# lcdconnector2.net
KiCad netlist of a schematic drawn in EAGLE
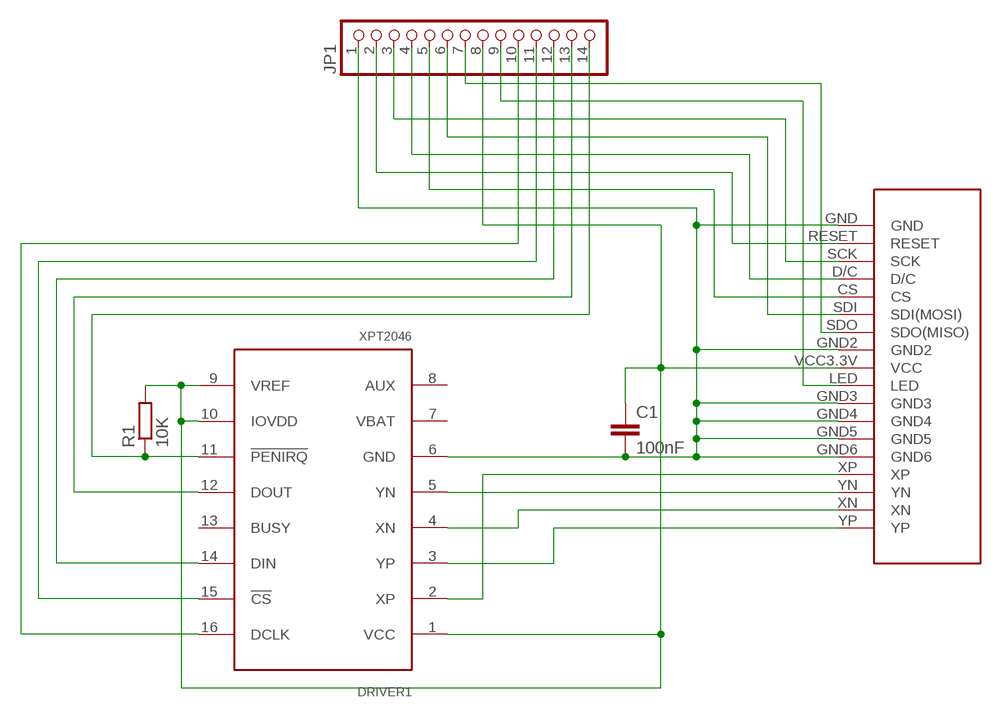
[diagram p0: schematic, sheet 1]

(export (version "E")
  (design (tool "Eeschema 10.0.6"))
  (components
    (comp (ref "C1")
      (value "100nF")
      (footprint "eagle-import:C0805K")
      (libsource (lib "eagle-import") (part "C-EUC0805K"))
    )
    (comp (ref "CONNECTOR1")
      (value "TJCTM24024-PINS")
      (footprint "eagle-import:TJCTM24024-PINS")
      (libsource (lib "eagle-import") (part "TJCTM24024-PINS"))
    )
    (comp (ref "DRIVER1")
      (value "XPT2046")
      (footprint "eagle-import:XPT2046")
      (libsource (lib "eagle-import") (part "XPT2046"))
    )
    (comp (ref "JP1")
      (value "PINHD-1X14-CB")
      (footprint "eagle-import:1X14-CB")
      (libsource (lib "eagle-import") (part "PINHD-1X14-CB"))
    )
    (comp (ref "R1")
      (value "10K")
      (footprint "eagle-import:M0805")
      (libsource (lib "eagle-import") (part "R-EU_M0805"))
    )
  )
  (nets
    (net (code "1") (name "Net-(CONNECTOR1-PadCS)") (class "Default")
      (node (ref "CONNECTOR1") (pin "CS") (pinfunction "CS_CS") (pintype "bidirectional"))
      (node (ref "JP1") (pin "5") (pinfunction "5_5") (pintype "passive"))
    )
    (net (code "2") (name "Net-(CONNECTOR1-PadD{slash}C)") (class "Default")
      (node (ref "CONNECTOR1") (pin "D/C") (pinfunction "D/C_D/C") (pintype "bidirectional"))
      (node (ref "JP1") (pin "4") (pinfunction "4_4") (pintype "passive"))
    )
    (net (code "3") (name "Net-(CONNECTOR1-PadLED)") (class "Default")
      (node (ref "CONNECTOR1") (pin "LED") (pinfunction "LED_LED") (pintype "bidirectional"))
      (node (ref "JP1") (pin "9") (pinfunction "9_9") (pintype "passive"))
    )
    (net (code "4") (name "Net-(CONNECTOR1-PadRESET)") (class "Default")
      (node (ref "CONNECTOR1") (pin "RESET") (pinfunction "RESET_RESET") (pintype "bidirectional"))
      (node (ref "JP1") (pin "2") (pinfunction "2_2") (pintype "passive"))
    )
    (net (code "5") (name "Net-(CONNECTOR1-PadSCK)") (class "Default")
      (node (ref "CONNECTOR1") (pin "SCK") (pinfunction "SCK_SCK") (pintype "bidirectional"))
      (node (ref "JP1") (pin "3") (pinfunction "3_3") (pintype "passive"))
    )
    (net (code "6") (name "Net-(CONNECTOR1-SDI(MOSI))") (class "Default")
      (node (ref "CONNECTOR1") (pin "SDI") (pinfunction "SDI(MOSI)_SDI") (pintype "bidirectional"))
      (node (ref "JP1") (pin "6") (pinfunction "6_6") (pintype "passive"))
    )
    (net (code "7") (name "Net-(CONNECTOR1-SDO(MISO))") (class "Default")
      (node (ref "CONNECTOR1") (pin "SDO") (pinfunction "SDO(MISO)_SDO") (pintype "bidirectional"))
      (node (ref "JP1") (pin "7") (pinfunction "7_7") (pintype "passive"))
    )
    (net (code "8") (name "Net-(CONNECTOR1-VCC)") (class "Default")
      (node (ref "C1") (pin "1") (pinfunction "1_1") (pintype "passive"))
      (node (ref "CONNECTOR1") (pin "VCC3.3V") (pinfunction "VCC_VCC3.3V") (pintype "bidirectional"))
      (node (ref "DRIVER1") (pin "1") (pinfunction "VCC_1") (pintype "bidirectional"))
      (node (ref "DRIVER1") (pin "10") (pinfunction "IOVDD_10") (pintype "bidirectional"))
      (node (ref "DRIVER1") (pin "9") (pinfunction "VREF_9") (pintype "bidirectional"))
      (node (ref "JP1") (pin "8") (pinfunction "8_8") (pintype "passive"))
      (node (ref "R1") (pin "2") (pinfunction "2_2") (pintype "passive"))
    )
    (net (code "9") (name "Net-(DRIVER1-DCLK)") (class "Default")
      (node (ref "DRIVER1") (pin "16") (pinfunction "DCLK_16") (pintype "bidirectional"))
      (node (ref "JP1") (pin "10") (pinfunction "10_10") (pintype "passive"))
    )
    (net (code "10") (name "Net-(DRIVER1-DIN)") (class "Default")
      (node (ref "DRIVER1") (pin "14") (pinfunction "DIN_14") (pintype "bidirectional"))
      (node (ref "JP1") (pin "12") (pinfunction "12_12") (pintype "passive"))
    )
    (net (code "11") (name "Net-(DRIVER1-DOUT)") (class "Default")
      (node (ref "DRIVER1") (pin "12") (pinfunction "DOUT_12") (pintype "bidirectional"))
      (node (ref "JP1") (pin "13") (pinfunction "13_13") (pintype "passive"))
    )
    (net (code "12") (name "Net-(DRIVER1-GND)") (class "Default")
      (node (ref "C1") (pin "2") (pinfunction "2_2") (pintype "passive"))
      (node (ref "CONNECTOR1") (pin "GND") (pinfunction "GND_GND") (pintype "bidirectional"))
      (node (ref "CONNECTOR1") (pin "GND2") (pinfunction "GND2_GND2") (pintype "bidirectional"))
      (node (ref "CONNECTOR1") (pin "GND3") (pinfunction "GND3_GND3") (pintype "bidirectional"))
      (node (ref "CONNECTOR1") (pin "GND4") (pinfunction "GND4_GND4") (pintype "bidirectional"))
      (node (ref "CONNECTOR1") (pin "GND5") (pinfunction "GND5_GND5") (pintype "bidirectional"))
      (node (ref "CONNECTOR1") (pin "GND6") (pinfunction "GND6_GND6") (pintype "bidirectional"))
      (node (ref "DRIVER1") (pin "6") (pinfunction "GND_6") (pintype "bidirectional"))
      (node (ref "JP1") (pin "1") (pinfunction "1_1") (pintype "passive"))
    )
    (net (code "13") (name "Net-(DRIVER1-XN)") (class "Default")
      (node (ref "CONNECTOR1") (pin "XN") (pinfunction "XN_XN") (pintype "bidirectional"))
      (node (ref "DRIVER1") (pin "4") (pinfunction "XN_4") (pintype "bidirectional"))
    )
    (net (code "14") (name "Net-(DRIVER1-XP)") (class "Default")
      (node (ref "CONNECTOR1") (pin "XP") (pinfunction "XP_XP") (pintype "bidirectional"))
      (node (ref "DRIVER1") (pin "2") (pinfunction "XP_2") (pintype "bidirectional"))
    )
    (net (code "15") (name "Net-(DRIVER1-YN)") (class "Default")
      (node (ref "CONNECTOR1") (pin "YN") (pinfunction "YN_YN") (pintype "bidirectional"))
      (node (ref "DRIVER1") (pin "5") (pinfunction "YN_5") (pintype "bidirectional"))
    )
    (net (code "16") (name "Net-(DRIVER1-YP)") (class "Default")
      (node (ref "CONNECTOR1") (pin "YP") (pinfunction "YP_YP") (pintype "bidirectional"))
      (node (ref "DRIVER1") (pin "3") (pinfunction "YP_3") (pintype "bidirectional"))
    )
    (net (code "17") (name "Net-(DRIVER1-~{CS})") (class "Default")
      (node (ref "DRIVER1") (pin "15") (pinfunction "~{CS}_15") (pintype "bidirectional"))
      (node (ref "JP1") (pin "11") (pinfunction "11_11") (pintype "passive"))
    )
    (net (code "18") (name "Net-(DRIVER1-~{PENIRQ})") (class "Default")
      (node (ref "DRIVER1") (pin "11") (pinfunction "~{PENIRQ}_11") (pintype "bidirectional"))
      (node (ref "JP1") (pin "14") (pinfunction "14_14") (pintype "passive"))
      (node (ref "R1") (pin "1") (pinfunction "1_1") (pintype "passive"))
    )
    (net (code "19") (name "unconnected-(DRIVER1-AUX-Pad8)") (class "Default")
      (node (ref "DRIVER1") (pin "8") (pinfunction "AUX_8") (pintype "bidirectional"))
    )
    (net (code "20") (name "unconnected-(DRIVER1-BUSY-Pad13)") (class "Default")
      (node (ref "DRIVER1") (pin "13") (pinfunction "BUSY_13") (pintype "bidirectional"))
    )
    (net (code "21") (name "unconnected-(DRIVER1-VBAT-Pad7)") (class "Default")
      (node (ref "DRIVER1") (pin "7") (pinfunction "VBAT_7") (pintype "bidirectional"))
    )
  )
)
